# SCH_ina3221_2022-09-22.net
KiCad netlist of a schematic drawn in EasyEDA
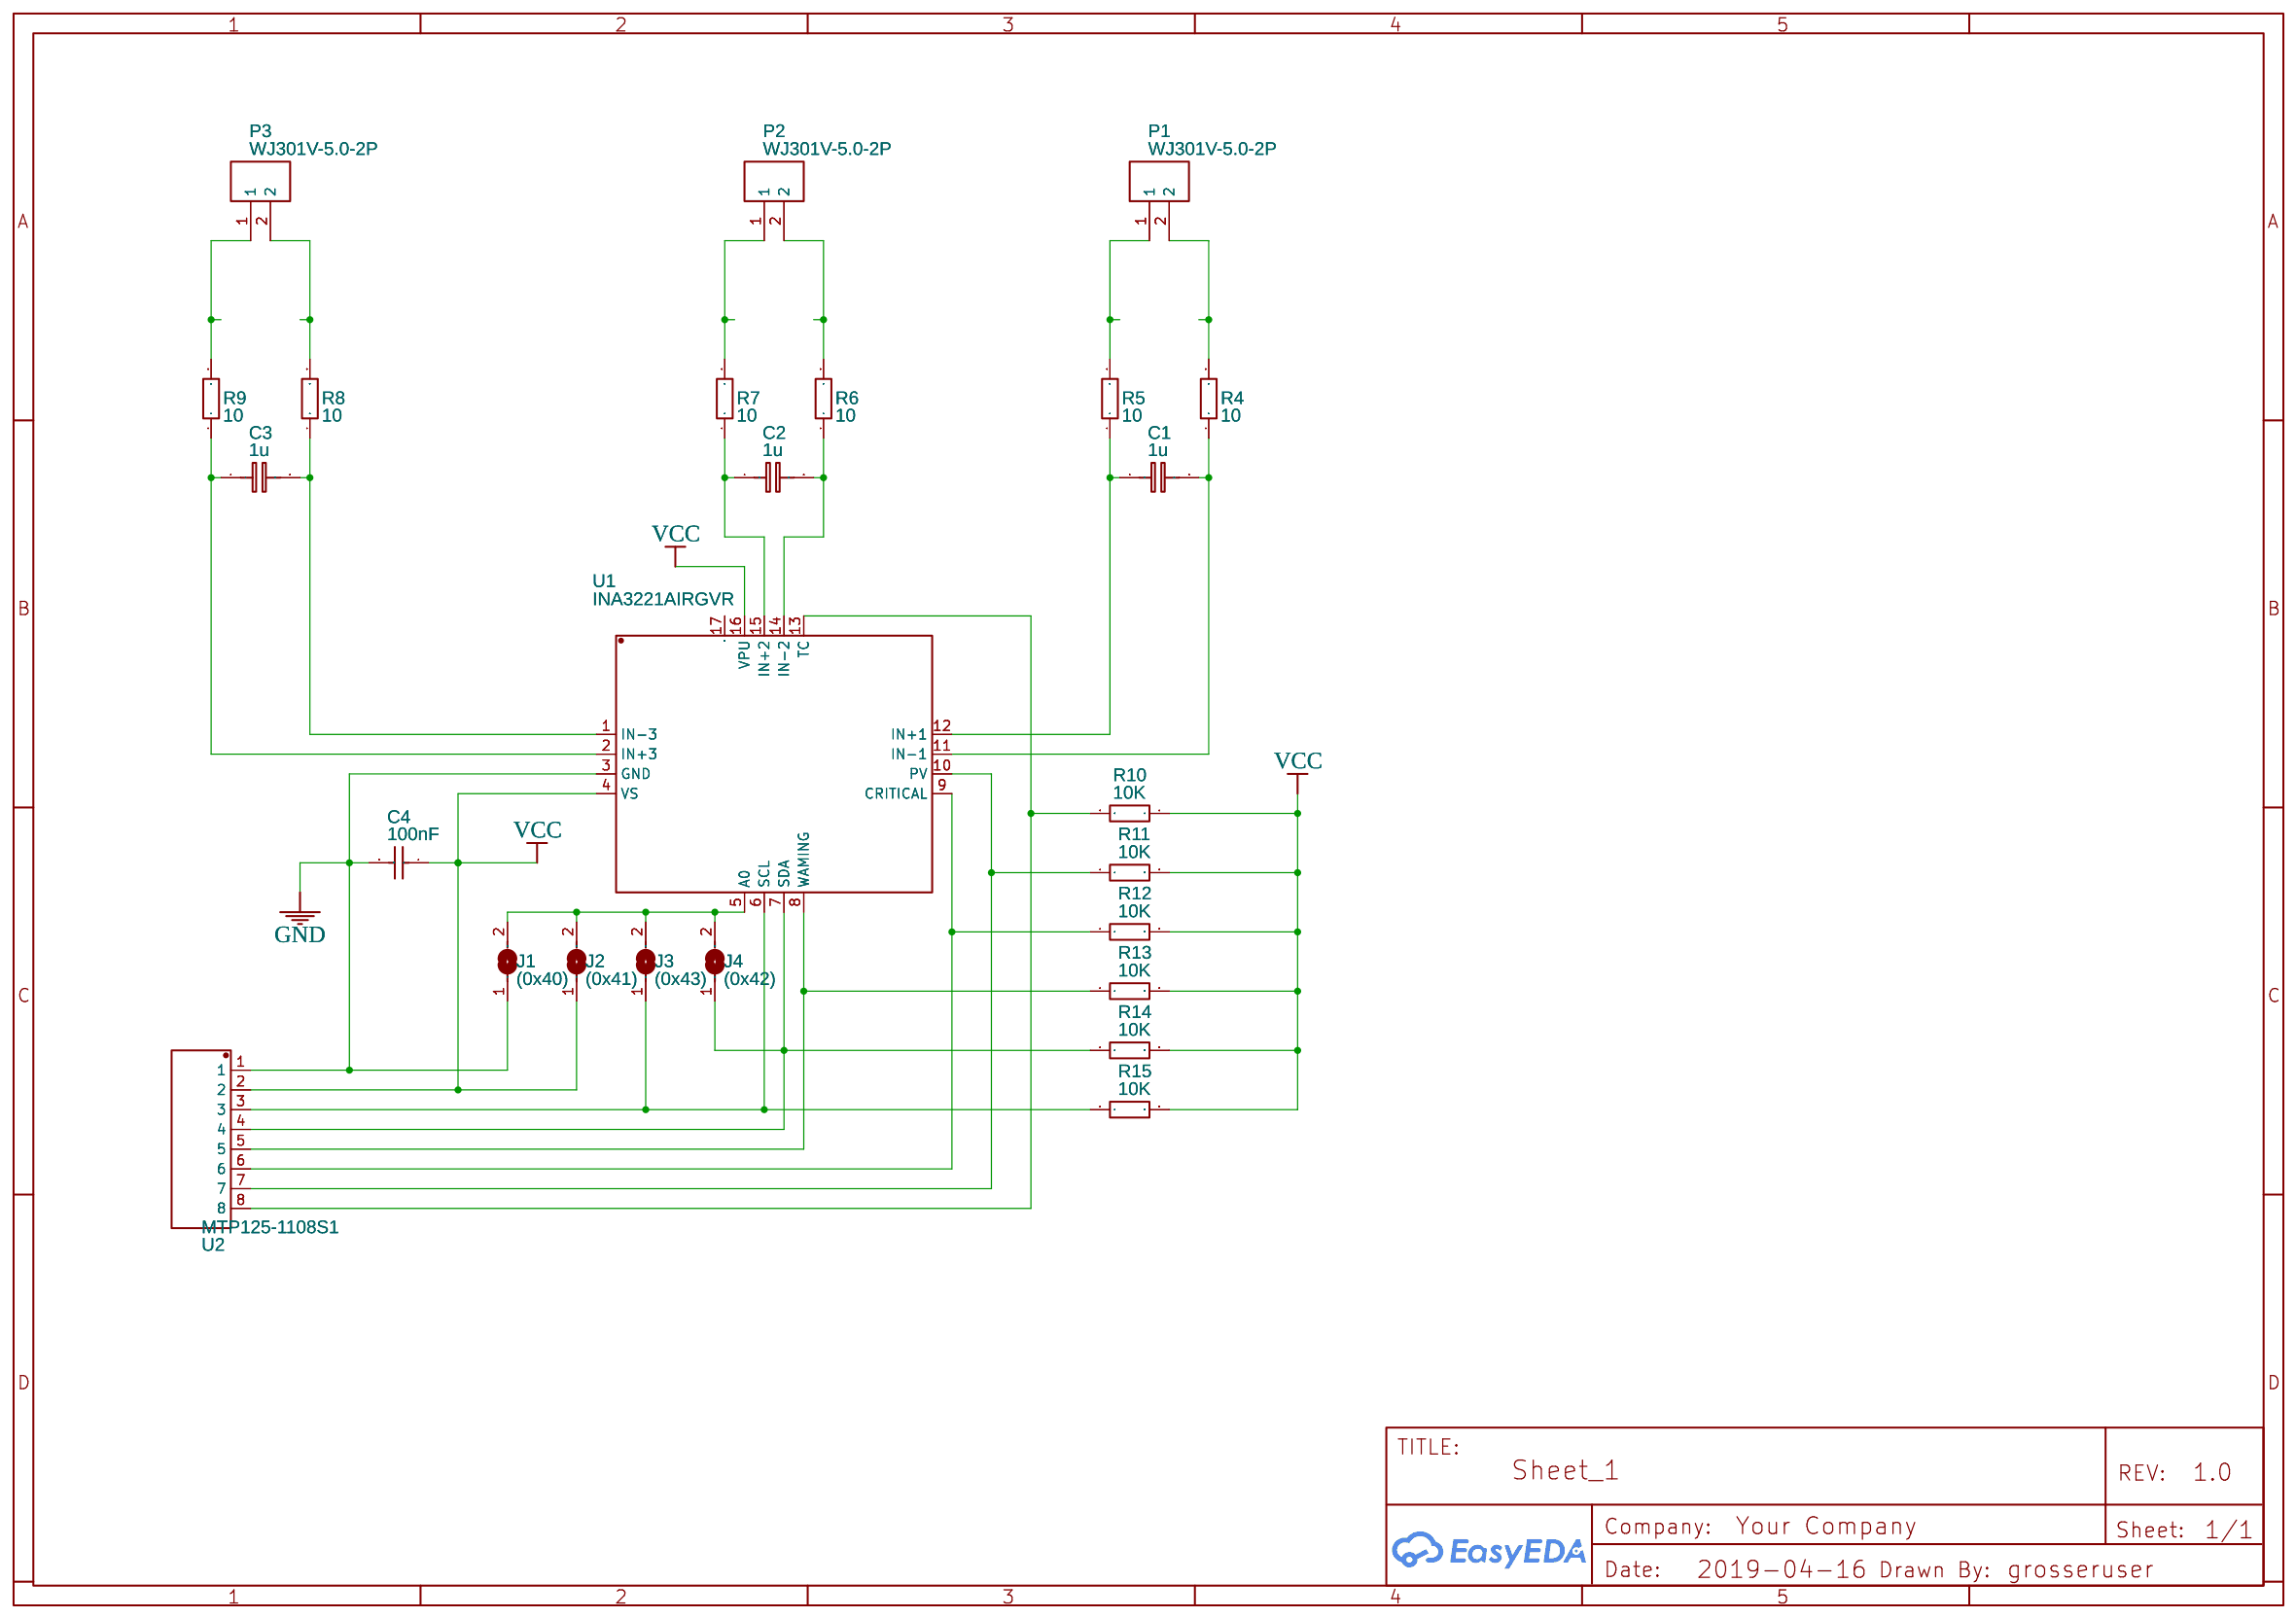
[diagram p0: schematic sheet]

(export (version "E")
  (design (tool "Eeschema 10.0.6"))
  (components
    (comp (ref "C1")
      (value "1u")
      (fields (field (name "BOM_Manufacturer Part") "?") (field (name "BOM_Supplier Part") "C91186"))
      (libsource (lib "") (part "Cap_RAD-0.1_EU_1"))
    )
    (comp (ref "C2")
      (value "1u")
      (fields (field (name "BOM_Manufacturer Part") "?") (field (name "BOM_Supplier Part") "C91186"))
      (libsource (lib "") (part "Cap_RAD-0.1_EU"))
    )
    (comp (ref "C3")
      (value "1u")
      (fields (field (name "BOM_Manufacturer Part") "?") (field (name "BOM_Supplier Part") "C91186"))
      (libsource (lib "") (part "Cap_RAD-0.1_EU_1"))
    )
    (comp (ref "C4")
      (value "100nF")
      (fields
        (field (name "BOM_Manufacturer Part") "TCC0805X7R104M500DT")
        (field (name "BOM_Supplier Part") "C360619")
      )
      (libsource (lib "") (part "TCC0805X7R104M500DT"))
    )
    (comp (ref "J1")
      (value "(0x40)")
      (fields (field (name "BOM_Manufacturer Part") "?"))
      (libsource (lib "") (part "Unknown_250_470"))
    )
    (comp (ref "J2")
      (value "(0x41)")
      (fields (field (name "BOM_Manufacturer Part") "?"))
      (libsource (lib "") (part "Unknown_285_470"))
    )
    (comp (ref "J3")
      (value "(0x43)")
      (fields (field (name "BOM_Manufacturer Part") "?"))
      (libsource (lib "") (part "Unknown_320_470"))
    )
    (comp (ref "J4")
      (value "(0x42)")
      (fields (field (name "BOM_Manufacturer Part") "?"))
      (libsource (lib "") (part "Unknown_355_470"))
    )
    (comp (ref "P1")
      (value "WJ301V-5.0-2P")
      (fields (field (name "BOM_Supplier Part") "C8475"))
      (libsource (lib "") (part "Unknown_580_95"))
    )
    (comp (ref "P2")
      (value "WJ301V-5.0-2P")
      (fields (field (name "BOM_Supplier Part") "C8475"))
      (libsource (lib "") (part "Unknown_385_95"))
    )
    (comp (ref "P3")
      (value "WJ301V-5.0-2P")
      (fields (field (name "BOM_Supplier Part") "C8475"))
      (libsource (lib "") (part "Unknown_125_95"))
    )
    (comp (ref "R4")
      (value "10")
      (fields (field (name "BOM_Manufacturer Part") "?") (field (name "BOM_Supplier Part") "C25278"))
      (libsource (lib "") (part "Res_AXIAL-0.3(1/8W)_EU"))
    )
    (comp (ref "R5")
      (value "10")
      (fields (field (name "BOM_Manufacturer Part") "?") (field (name "BOM_Supplier Part") "C25278"))
      (libsource (lib "") (part "Res_AXIAL-0.3(1/8W)_EU"))
    )
    (comp (ref "R6")
      (value "10")
      (fields (field (name "BOM_Manufacturer Part") "?") (field (name "BOM_Supplier Part") "C25278"))
      (libsource (lib "") (part "Res_AXIAL-0.3(1/8W)_EU"))
    )
    (comp (ref "R7")
      (value "10")
      (fields (field (name "BOM_Manufacturer Part") "?") (field (name "BOM_Supplier Part") "C25278"))
      (libsource (lib "") (part "Res_AXIAL-0.3(1/8W)_EU"))
    )
    (comp (ref "R8")
      (value "10")
      (fields (field (name "BOM_Manufacturer Part") "?") (field (name "BOM_Supplier Part") "C25278"))
      (libsource (lib "") (part "Res_AXIAL-0.3(1/8W)_EU"))
    )
    (comp (ref "R9")
      (value "10")
      (fields (field (name "BOM_Manufacturer Part") "?") (field (name "BOM_Supplier Part") "C25278"))
      (libsource (lib "") (part "Res_AXIAL-0.3(1/8W)_EU"))
    )
    (comp (ref "R10")
      (value "10K")
      (fields
        (field (name "BOM_Manufacturer Part") "0805W8J0103T5E")
        (field (name "BOM_Supplier Part") "C25612")
      )
      (libsource (lib "") (part "0805W8J0103T5E_1"))
    )
    (comp (ref "R11")
      (value "10K")
      (fields
        (field (name "BOM_Manufacturer Part") "0805W8J0103T5E")
        (field (name "BOM_Supplier Part") "C25612")
      )
      (libsource (lib "") (part "0805W8J0103T5E"))
    )
    (comp (ref "R12")
      (value "10K")
      (fields
        (field (name "BOM_Manufacturer Part") "0805W8J0103T5E")
        (field (name "BOM_Supplier Part") "C25612")
      )
      (libsource (lib "") (part "0805W8J0103T5E"))
    )
    (comp (ref "R13")
      (value "10K")
      (fields
        (field (name "BOM_Manufacturer Part") "0805W8J0103T5E")
        (field (name "BOM_Supplier Part") "C25612")
      )
      (libsource (lib "") (part "0805W8J0103T5E"))
    )
    (comp (ref "R14")
      (value "10K")
      (fields
        (field (name "BOM_Manufacturer Part") "0805W8J0103T5E")
        (field (name "BOM_Supplier Part") "C25612")
      )
      (libsource (lib "") (part "0805W8J0103T5E"))
    )
    (comp (ref "R15")
      (value "10K")
      (fields
        (field (name "BOM_Manufacturer Part") "0805W8J0103T5E")
        (field (name "BOM_Supplier Part") "C25612")
      )
      (libsource (lib "") (part "0805W8J0103T5E"))
    )
    (comp (ref "U1")
      (value "INA3221AIRGVR")
      (fields (field (name "BOM_Supplier Part") "C181255"))
      (libsource (lib "") (part "Unknown_385_380"))
    )
    (comp (ref "U2")
      (value "MTP125-1108S1")
      (fields (field (name "BOM_Supplier Part") "C358689"))
      (libsource (lib "") (part "Unknown_100_570"))
    )
  )
  (nets
    (net (code "1") (name "GND") (class "Default")
      (node (ref "C4") (pin "2") (pinfunction "2_2") (pintype "input"))
      (node (ref "J1") (pin "1") (pinfunction "1_1") (pintype "bidirectional"))
      (node (ref "U1") (pin "3") (pinfunction "GND_3") (pintype "unspecified"))
      (node (ref "U2") (pin "1") (pinfunction "1_1") (pintype "unspecified"))
    )
    (net (code "2") (name "Net-(P1-Pad1)") (class "Default")
      (node (ref "P1") (pin "1") (pinfunction "1_1") (pintype "unspecified"))
      (node (ref "R5") (pin "2") (pinfunction "2_2") (pintype "unspecified"))
    )
    (net (code "3") (name "Net-(P1-Pad2)") (class "Default")
      (node (ref "P1") (pin "2") (pinfunction "2_2") (pintype "unspecified"))
      (node (ref "R4") (pin "2") (pinfunction "2_2") (pintype "unspecified"))
    )
    (net (code "4") (name "Net-(P2-Pad1)") (class "Default")
      (node (ref "P2") (pin "1") (pinfunction "1_1") (pintype "unspecified"))
      (node (ref "R7") (pin "2") (pinfunction "2_2") (pintype "unspecified"))
    )
    (net (code "5") (name "Net-(P2-Pad2)") (class "Default")
      (node (ref "P2") (pin "2") (pinfunction "2_2") (pintype "unspecified"))
      (node (ref "R6") (pin "2") (pinfunction "2_2") (pintype "unspecified"))
    )
    (net (code "6") (name "Net-(P3-Pad1)") (class "Default")
      (node (ref "P3") (pin "1") (pinfunction "1_1") (pintype "unspecified"))
      (node (ref "R9") (pin "2") (pinfunction "2_2") (pintype "unspecified"))
    )
    (net (code "7") (name "Net-(P3-Pad2)") (class "Default")
      (node (ref "P3") (pin "2") (pinfunction "2_2") (pintype "unspecified"))
      (node (ref "R8") (pin "2") (pinfunction "2_2") (pintype "unspecified"))
    )
    (net (code "8") (name "Net-(U1-A0)") (class "Default")
      (node (ref "J1") (pin "2") (pinfunction "2_2") (pintype "bidirectional"))
      (node (ref "J2") (pin "2") (pinfunction "2_2") (pintype "bidirectional"))
      (node (ref "J3") (pin "2") (pinfunction "2_2") (pintype "bidirectional"))
      (node (ref "J4") (pin "2") (pinfunction "2_2") (pintype "bidirectional"))
      (node (ref "U1") (pin "5") (pinfunction "A0_5") (pintype "unspecified"))
    )
    (net (code "9") (name "Net-(U1-CRITICAL)") (class "Default")
      (node (ref "R12") (pin "1") (pinfunction "1_1") (pintype "input"))
      (node (ref "U1") (pin "9") (pinfunction "CRITICAL_9") (pintype "unspecified"))
      (node (ref "U2") (pin "6") (pinfunction "6_6") (pintype "unspecified"))
    )
    (net (code "10") (name "Net-(U1-IN+1)") (class "Default")
      (node (ref "C1") (pin "1") (pinfunction "1_1") (pintype "unspecified"))
      (node (ref "R5") (pin "1") (pinfunction "1_1") (pintype "unspecified"))
      (node (ref "U1") (pin "12") (pinfunction "IN+1_12") (pintype "unspecified"))
    )
    (net (code "11") (name "Net-(U1-IN+2)") (class "Default")
      (node (ref "C2") (pin "1") (pinfunction "1_1") (pintype "unspecified"))
      (node (ref "R7") (pin "1") (pinfunction "1_1") (pintype "unspecified"))
      (node (ref "U1") (pin "15") (pinfunction "IN+2_15") (pintype "unspecified"))
    )
    (net (code "12") (name "Net-(U1-IN+3)") (class "Default")
      (node (ref "C3") (pin "1") (pinfunction "1_1") (pintype "unspecified"))
      (node (ref "R9") (pin "1") (pinfunction "1_1") (pintype "unspecified"))
      (node (ref "U1") (pin "2") (pinfunction "IN+3_2") (pintype "unspecified"))
    )
    (net (code "13") (name "Net-(U1-IN-1)") (class "Default")
      (node (ref "C1") (pin "2") (pinfunction "2_2") (pintype "unspecified"))
      (node (ref "R4") (pin "1") (pinfunction "1_1") (pintype "unspecified"))
      (node (ref "U1") (pin "11") (pinfunction "IN-1_11") (pintype "unspecified"))
    )
    (net (code "14") (name "Net-(U1-IN-2)") (class "Default")
      (node (ref "C2") (pin "2") (pinfunction "2_2") (pintype "unspecified"))
      (node (ref "R6") (pin "1") (pinfunction "1_1") (pintype "unspecified"))
      (node (ref "U1") (pin "14") (pinfunction "IN-2_14") (pintype "unspecified"))
    )
    (net (code "15") (name "Net-(U1-IN-3)") (class "Default")
      (node (ref "C3") (pin "2") (pinfunction "2_2") (pintype "unspecified"))
      (node (ref "R8") (pin "1") (pinfunction "1_1") (pintype "unspecified"))
      (node (ref "U1") (pin "1") (pinfunction "IN-3_1") (pintype "unspecified"))
    )
    (net (code "16") (name "Net-(U1-PV)") (class "Default")
      (node (ref "R11") (pin "1") (pinfunction "1_1") (pintype "input"))
      (node (ref "U1") (pin "10") (pinfunction "PV_10") (pintype "unspecified"))
      (node (ref "U2") (pin "7") (pinfunction "7_7") (pintype "unspecified"))
    )
    (net (code "17") (name "Net-(U1-SCL)") (class "Default")
      (node (ref "J3") (pin "1") (pinfunction "1_1") (pintype "bidirectional"))
      (node (ref "R15") (pin "1") (pinfunction "1_1") (pintype "input"))
      (node (ref "U1") (pin "6") (pinfunction "SCL_6") (pintype "unspecified"))
      (node (ref "U2") (pin "3") (pinfunction "3_3") (pintype "unspecified"))
    )
    (net (code "18") (name "Net-(U1-SDA)") (class "Default")
      (node (ref "J4") (pin "1") (pinfunction "1_1") (pintype "bidirectional"))
      (node (ref "R14") (pin "1") (pinfunction "1_1") (pintype "input"))
      (node (ref "U1") (pin "7") (pinfunction "SDA_7") (pintype "unspecified"))
      (node (ref "U2") (pin "4") (pinfunction "4_4") (pintype "unspecified"))
    )
    (net (code "19") (name "Net-(U1-TC)") (class "Default")
      (node (ref "R10") (pin "2") (pinfunction "2_2") (pintype "input"))
      (node (ref "U1") (pin "13") (pinfunction "TC_13") (pintype "unspecified"))
      (node (ref "U2") (pin "8") (pinfunction "8_8") (pintype "unspecified"))
    )
    (net (code "20") (name "Net-(U1-WAMING)") (class "Default")
      (node (ref "R13") (pin "1") (pinfunction "1_1") (pintype "input"))
      (node (ref "U1") (pin "8") (pinfunction "WAMING_8") (pintype "unspecified"))
      (node (ref "U2") (pin "5") (pinfunction "5_5") (pintype "unspecified"))
    )
    (net (code "21") (name "VCC") (class "Default")
      (node (ref "C4") (pin "1") (pinfunction "1_1") (pintype "input"))
      (node (ref "J2") (pin "1") (pinfunction "1_1") (pintype "bidirectional"))
      (node (ref "R10") (pin "1") (pinfunction "1_1") (pintype "input"))
      (node (ref "R11") (pin "2") (pinfunction "2_2") (pintype "input"))
      (node (ref "R12") (pin "2") (pinfunction "2_2") (pintype "input"))
      (node (ref "R13") (pin "2") (pinfunction "2_2") (pintype "input"))
      (node (ref "R14") (pin "2") (pinfunction "2_2") (pintype "input"))
      (node (ref "R15") (pin "2") (pinfunction "2_2") (pintype "input"))
      (node (ref "U1") (pin "16") (pinfunction "VPU_16") (pintype "unspecified"))
      (node (ref "U1") (pin "4") (pinfunction "VS_4") (pintype "unspecified"))
      (node (ref "U2") (pin "2") (pinfunction "2_2") (pintype "unspecified"))
    )
    (net (code "22") (name "unconnected-(U1-PAD-Pad17)") (class "Default")
      (node (ref "U1") (pin "17") (pinfunction "PAD_17") (pintype "unspecified"))
    )
  )
)
